# socket-v2-high-voltage-iotbee.net
KiCad netlist of a schematic drawn in EAGLE
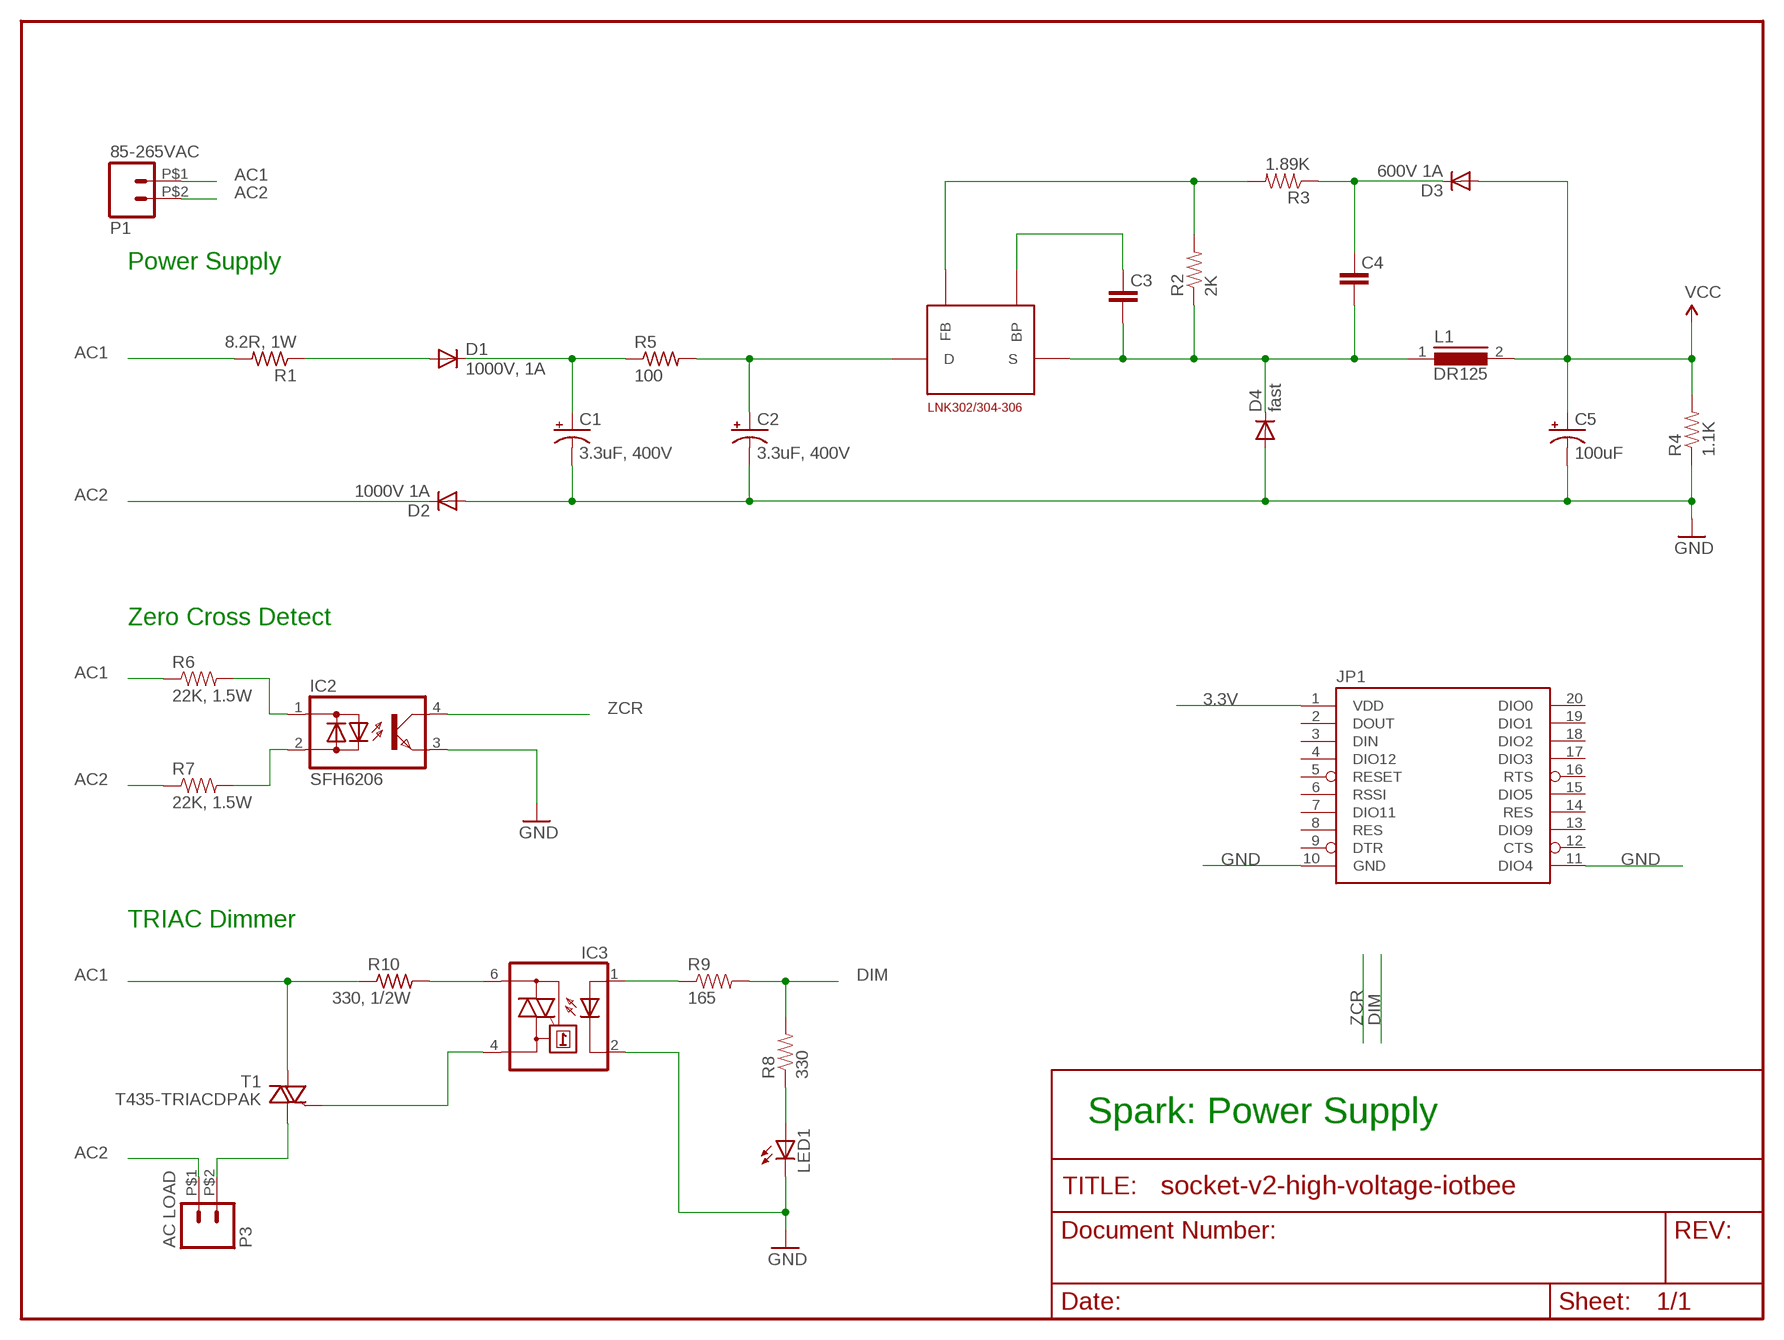
[diagram p0: schematic, sheet 1]

(export (version "E")
  (design (tool "Eeschema 10.0.6"))
  (components
    (comp (ref "C1")
      (value "3.3uF, 400V")
      (footprint "eagle-import:E3,5-8")
      (libsource (lib "eagle-import") (part "CPOL-USE3.5-8"))
    )
    (comp (ref "C2")
      (value "3.3uF, 400V")
      (footprint "eagle-import:E3,5-8")
      (libsource (lib "eagle-import") (part "CPOL-USE3.5-8"))
    )
    (comp (ref "C3")
      (value "0.1uF")
      (footprint "eagle-import:0603-CAP")
      (libsource (lib "eagle-import") (part "CAP0603-CAP"))
    )
    (comp (ref "C4")
      (value "10uF, 50V")
      (footprint "eagle-import:0805")
      (libsource (lib "eagle-import") (part "CAP0805"))
    )
    (comp (ref "C5")
      (value "100uF")
      (footprint "eagle-import:EIA3528")
      (libsource (lib "eagle-import") (part "CAP_POL3528"))
    )
    (comp (ref "D1")
      (value "1000V, 1A")
      (footprint "eagle-import:SMA-DIODE")
      (libsource (lib "eagle-import") (part "DIODESMA"))
    )
    (comp (ref "D2")
      (value "1000V 1A")
      (footprint "eagle-import:SMA-DIODE")
      (libsource (lib "eagle-import") (part "DIODESMA"))
    )
    (comp (ref "D3")
      (value "600V 1A")
      (footprint "eagle-import:SMA-DIODE")
      (libsource (lib "eagle-import") (part "DIODESMA"))
    )
    (comp (ref "D4")
      (value "fast")
      (footprint "eagle-import:SMA-DIODE")
      (libsource (lib "eagle-import") (part "DIODESMA"))
    )
    (comp (ref "IC1")
      (value "LNK302/304-306")
      (footprint "eagle-import:SMD-8B")
      (libsource (lib "eagle-import") (part "LNK302/304-306"))
    )
    (comp (ref "IC2")
      (value "SFH6206")
      (footprint "eagle-import:DIL4-SMD")
      (fields (field (name "MF") "VISHAY/TELEFUNKEN") (field (name "MPN") "SFH6206-3"))
      (libsource (lib "eagle-import") (part "SFH6206"))
    )
    (comp (ref "IC3")
      (value "MOC3031S")
      (footprint "eagle-import:DIL6-SMD")
      (fields
        (field (name "MF") "FAIRCHILD SEMICONDUCTOR")
        (field (name "MPN") "MOC3031SM")
        (field (name "MPN_1") "MOC3031SM")
        (field (name "OC_FARNELL") "unknown")
        (field (name "OC_NEWARK") "34C1335")
      )
      (libsource (lib "eagle-import") (part "MOC30S31"))
    )
    (comp (ref "JP1")
      (value "XBEE-1B3")
      (footprint "eagle-import:XBEE-SMD")
      (libsource (lib "eagle-import") (part "XBEE-1B3"))
    )
    (comp (ref "L1")
      (value "DR125")
      (footprint "eagle-import:DR125")
      (libsource (lib "eagle-import") (part "DR125"))
    )
    (comp (ref "LED1")
      (value "LED0603")
      (footprint "eagle-import:LED-0603")
      (libsource (lib "eagle-import") (part "LED0603"))
    )
    (comp (ref "P1")
      (value "85-265VAC")
      (footprint "eagle-import:1X02_BIG")
      (libsource (lib "eagle-import") (part "M02PTH2"))
    )
    (comp (ref "P3")
      (value "AC LOAD")
      (footprint "eagle-import:1X02_BIG")
      (libsource (lib "eagle-import") (part "M02PTH2"))
    )
    (comp (ref "R1")
      (value "8.2R, 1W")
      (footprint "eagle-import:0207_10")
      (libsource (lib "eagle-import") (part "R-US_0207/10"))
    )
    (comp (ref "R2")
      (value "2K")
      (footprint "eagle-import:0805")
      (libsource (lib "eagle-import") (part "RESISTOR0805-RES"))
    )
    (comp (ref "R3")
      (value "1.89K")
      (footprint "eagle-import:0805")
      (libsource (lib "eagle-import") (part "RESISTOR0805-RES"))
    )
    (comp (ref "R4")
      (value "1.1K")
      (footprint "eagle-import:0603-RES")
      (libsource (lib "eagle-import") (part "RESISTOR0603-RES"))
    )
    (comp (ref "R5")
      (value "100")
      (footprint "eagle-import:0204_7")
      (libsource (lib "eagle-import") (part "R-US_0204/7"))
    )
    (comp (ref "R6")
      (value "22K, 1.5W")
      (footprint "eagle-import:R2512")
      (libsource (lib "eagle-import") (part "RESISTOR2512"))
    )
    (comp (ref "R7")
      (value "22K, 1.5W")
      (footprint "eagle-import:R2512")
      (libsource (lib "eagle-import") (part "RESISTOR2512"))
    )
    (comp (ref "R8")
      (value "330")
      (footprint "eagle-import:0805")
      (libsource (lib "eagle-import") (part "RESISTOR0805-RES"))
    )
    (comp (ref "R9")
      (value "165")
      (footprint "eagle-import:0805")
      (libsource (lib "eagle-import") (part "RESISTOR0805-RES"))
    )
    (comp (ref "R10")
      (value "330, 1/2W")
      (footprint "eagle-import:R1210")
      (libsource (lib "eagle-import") (part "R-US_R1210"))
    )
    (comp (ref "T1")
      (value "T435-TRIACDPAK")
      (footprint "eagle-import:TO252")
      (libsource (lib "eagle-import") (part "T435-TRIACDPAK"))
    )
  )
  (nets
    (net (code "1") (name "/AC1") (class "Default")
      (node (ref "P1") (pin "P$1") (pinfunction "1_P$1") (pintype "passive"))
      (node (ref "R1") (pin "2") (pinfunction "2_2") (pintype "passive"))
      (node (ref "R10") (pin "1") (pinfunction "1_1") (pintype "passive"))
      (node (ref "R6") (pin "1") (pinfunction "1_1") (pintype "passive"))
      (node (ref "T1") (pin "2") (pinfunction "A2_2") (pintype "passive"))
    )
    (net (code "2") (name "/AC2") (class "Default")
      (node (ref "D2") (pin "C") (pinfunction "C_C") (pintype "passive"))
      (node (ref "P1") (pin "P$2") (pinfunction "2_P$2") (pintype "passive"))
      (node (ref "P3") (pin "P$1") (pinfunction "1_P$1") (pintype "passive"))
      (node (ref "R7") (pin "1") (pinfunction "1_1") (pintype "passive"))
    )
    (net (code "3") (name "/DIM") (class "Default")
      (node (ref "R8") (pin "2") (pinfunction "2_2") (pintype "passive"))
      (node (ref "R9") (pin "2") (pinfunction "2_2") (pintype "passive"))
    )
    (net (code "4") (name "/ZCR") (class "Default")
      (node (ref "IC2") (pin "4") (pinfunction "C_4") (pintype "passive"))
    )
    (net (code "5") (name "GND") (class "Default")
      (node (ref "C1") (pin "-") (pinfunction "-_-") (pintype "passive"))
      (node (ref "C2") (pin "-") (pinfunction "-_-") (pintype "passive"))
      (node (ref "C5") (pin "C") (pinfunction "-_C") (pintype "passive"))
      (node (ref "D2") (pin "A") (pinfunction "A_A") (pintype "passive"))
      (node (ref "D4") (pin "A") (pinfunction "A_A") (pintype "passive"))
      (node (ref "IC2") (pin "3") (pinfunction "E_3") (pintype "passive"))
      (node (ref "IC3") (pin "2") (pinfunction "C_2") (pintype "passive"))
      (node (ref "JP1") (pin "10") (pinfunction "GND_10") (pintype "power_in"))
      (node (ref "JP1") (pin "11") (pinfunction "DIO4_11") (pintype "bidirectional"))
      (node (ref "LED1") (pin "C") (pinfunction "C_C") (pintype "passive"))
      (node (ref "R4") (pin "1") (pinfunction "1_1") (pintype "passive"))
    )
    (net (code "6") (name "Net-(C1-Pad+)") (class "Default")
      (node (ref "C1") (pin "+") (pinfunction "+_+") (pintype "passive"))
      (node (ref "D1") (pin "C") (pinfunction "C_C") (pintype "passive"))
      (node (ref "R5") (pin "1") (pinfunction "1_1") (pintype "passive"))
    )
    (net (code "7") (name "Net-(C2-Pad+)") (class "Default")
      (node (ref "C2") (pin "+") (pinfunction "+_+") (pintype "passive"))
      (node (ref "IC1") (pin "D") (pinfunction "D_D") (pintype "bidirectional"))
      (node (ref "R5") (pin "2") (pinfunction "2_2") (pintype "passive"))
    )
    (net (code "8") (name "Net-(C3-Pad2)") (class "Default")
      (node (ref "C3") (pin "2") (pinfunction "2_2") (pintype "passive"))
      (node (ref "IC1") (pin "BP") (pinfunction "BP_BP") (pintype "bidirectional"))
    )
    (net (code "9") (name "Net-(C4-Pad2)") (class "Default")
      (node (ref "C4") (pin "2") (pinfunction "2_2") (pintype "passive"))
      (node (ref "D3") (pin "C") (pinfunction "C_C") (pintype "passive"))
      (node (ref "R3") (pin "1") (pinfunction "1_1") (pintype "passive"))
    )
    (net (code "10") (name "Net-(D1-PadA)") (class "Default")
      (node (ref "D1") (pin "A") (pinfunction "A_A") (pintype "passive"))
      (node (ref "R1") (pin "1") (pinfunction "1_1") (pintype "passive"))
    )
    (net (code "11") (name "Net-(IC1-PadFB)") (class "Default")
      (node (ref "IC1") (pin "FB") (pinfunction "FB_FB") (pintype "bidirectional"))
      (node (ref "R2") (pin "2") (pinfunction "2_2") (pintype "passive"))
      (node (ref "R3") (pin "2") (pinfunction "2_2") (pintype "passive"))
    )
    (net (code "12") (name "Net-(IC1-S)") (class "Default")
      (node (ref "C3") (pin "1") (pinfunction "1_1") (pintype "passive"))
      (node (ref "C4") (pin "1") (pinfunction "1_1") (pintype "passive"))
      (node (ref "D4") (pin "C") (pinfunction "C_C") (pintype "passive"))
      (node (ref "IC1") (pin "S1") (pinfunction "S_S1") (pintype "bidirectional"))
      (node (ref "L1") (pin "1") (pinfunction "1_1") (pintype "passive"))
      (node (ref "R2") (pin "1") (pinfunction "1_1") (pintype "passive"))
    )
    (net (code "13") (name "Net-(IC2-AC1)") (class "Default")
      (node (ref "IC2") (pin "1") (pinfunction "AC1_1") (pintype "passive"))
      (node (ref "R6") (pin "2") (pinfunction "2_2") (pintype "passive"))
    )
    (net (code "14") (name "Net-(IC2-AC2)") (class "Default")
      (node (ref "IC2") (pin "2") (pinfunction "AC2_2") (pintype "passive"))
      (node (ref "R7") (pin "2") (pinfunction "2_2") (pintype "passive"))
    )
    (net (code "15") (name "Net-(IC3-A)") (class "Default")
      (node (ref "IC3") (pin "1") (pinfunction "A_1") (pintype "passive"))
      (node (ref "R9") (pin "1") (pinfunction "1_1") (pintype "passive"))
    )
    (net (code "16") (name "Net-(IC3-A1)") (class "Default")
      (node (ref "IC3") (pin "4") (pinfunction "A1_4") (pintype "passive"))
      (node (ref "T1") (pin "3") (pinfunction "G_3") (pintype "passive"))
    )
    (net (code "17") (name "Net-(IC3-A2)") (class "Default")
      (node (ref "IC3") (pin "6") (pinfunction "A2_6") (pintype "passive"))
      (node (ref "R10") (pin "2") (pinfunction "2_2") (pintype "passive"))
    )
    (net (code "18") (name "Net-(LED1-PadA)") (class "Default")
      (node (ref "LED1") (pin "A") (pinfunction "A_A") (pintype "passive"))
      (node (ref "R8") (pin "1") (pinfunction "1_1") (pintype "passive"))
    )
    (net (code "19") (name "Net-(P3-2)") (class "Default")
      (node (ref "P3") (pin "P$2") (pinfunction "2_P$2") (pintype "passive"))
      (node (ref "T1") (pin "1") (pinfunction "A1_1") (pintype "passive"))
    )
    (net (code "20") (name "VCC") (class "Default")
      (node (ref "C5") (pin "A") (pinfunction "+_A") (pintype "passive"))
      (node (ref "D3") (pin "A") (pinfunction "A_A") (pintype "passive"))
      (node (ref "JP1") (pin "1") (pinfunction "VDD_1") (pintype "power_in"))
      (node (ref "L1") (pin "2") (pinfunction "2_2") (pintype "passive"))
      (node (ref "R4") (pin "2") (pinfunction "2_2") (pintype "passive"))
    )
    (net (code "21") (name "unconnected-(JP1-CTS-Pad12)") (class "Default")
      (node (ref "JP1") (pin "12") (pinfunction "CTS_12") (pintype "output"))
    )
    (net (code "22") (name "unconnected-(JP1-DIN-Pad3)") (class "Default")
      (node (ref "JP1") (pin "3") (pinfunction "DIN_3") (pintype "input"))
    )
    (net (code "23") (name "unconnected-(JP1-DIO0-Pad20)") (class "Default")
      (node (ref "JP1") (pin "20") (pinfunction "DIO0_20") (pintype "bidirectional"))
    )
    (net (code "24") (name "unconnected-(JP1-DIO1-Pad19)") (class "Default")
      (node (ref "JP1") (pin "19") (pinfunction "DIO1_19") (pintype "bidirectional"))
    )
    (net (code "25") (name "unconnected-(JP1-DIO2-Pad18)") (class "Default")
      (node (ref "JP1") (pin "18") (pinfunction "DIO2_18") (pintype "bidirectional"))
    )
    (net (code "26") (name "unconnected-(JP1-DIO3-Pad17)") (class "Default")
      (node (ref "JP1") (pin "17") (pinfunction "DIO3_17") (pintype "bidirectional"))
    )
    (net (code "27") (name "unconnected-(JP1-DIO5-Pad15)") (class "Default")
      (node (ref "JP1") (pin "15") (pinfunction "DIO5_15") (pintype "bidirectional"))
    )
    (net (code "28") (name "unconnected-(JP1-DIO9-Pad13)") (class "Default")
      (node (ref "JP1") (pin "13") (pinfunction "DIO9_13") (pintype "bidirectional"))
    )
    (net (code "29") (name "unconnected-(JP1-DIO11-Pad7)") (class "Default")
      (node (ref "JP1") (pin "7") (pinfunction "DIO11_7") (pintype "bidirectional"))
    )
    (net (code "30") (name "unconnected-(JP1-DIO12-Pad4)") (class "Default")
      (node (ref "JP1") (pin "4") (pinfunction "DIO12_4") (pintype "bidirectional"))
    )
    (net (code "31") (name "unconnected-(JP1-DOUT-Pad2)") (class "Default")
      (node (ref "JP1") (pin "2") (pinfunction "DOUT_2") (pintype "output"))
    )
    (net (code "32") (name "unconnected-(JP1-DTR-Pad9)") (class "Default")
      (node (ref "JP1") (pin "9") (pinfunction "DTR_9") (pintype "bidirectional"))
    )
    (net (code "33") (name "unconnected-(JP1-RES-Pad8)") (class "Default")
      (node (ref "JP1") (pin "8") (pinfunction "RES_8") (pintype "bidirectional"))
    )
    (net (code "34") (name "unconnected-(JP1-RES-Pad14)") (class "Default")
      (node (ref "JP1") (pin "14") (pinfunction "RES_14") (pintype "bidirectional"))
    )
    (net (code "35") (name "unconnected-(JP1-RESET-Pad5)") (class "Default")
      (node (ref "JP1") (pin "5") (pinfunction "RESET_5") (pintype "input"))
    )
    (net (code "36") (name "unconnected-(JP1-RSSI-Pad6)") (class "Default")
      (node (ref "JP1") (pin "6") (pinfunction "RSSI_6") (pintype "bidirectional"))
    )
    (net (code "37") (name "unconnected-(JP1-RTS-Pad16)") (class "Default")
      (node (ref "JP1") (pin "16") (pinfunction "RTS_16") (pintype "input"))
    )
  )
)
